# MICRO.net
KiCad netlist of a schematic drawn in Altium Designer
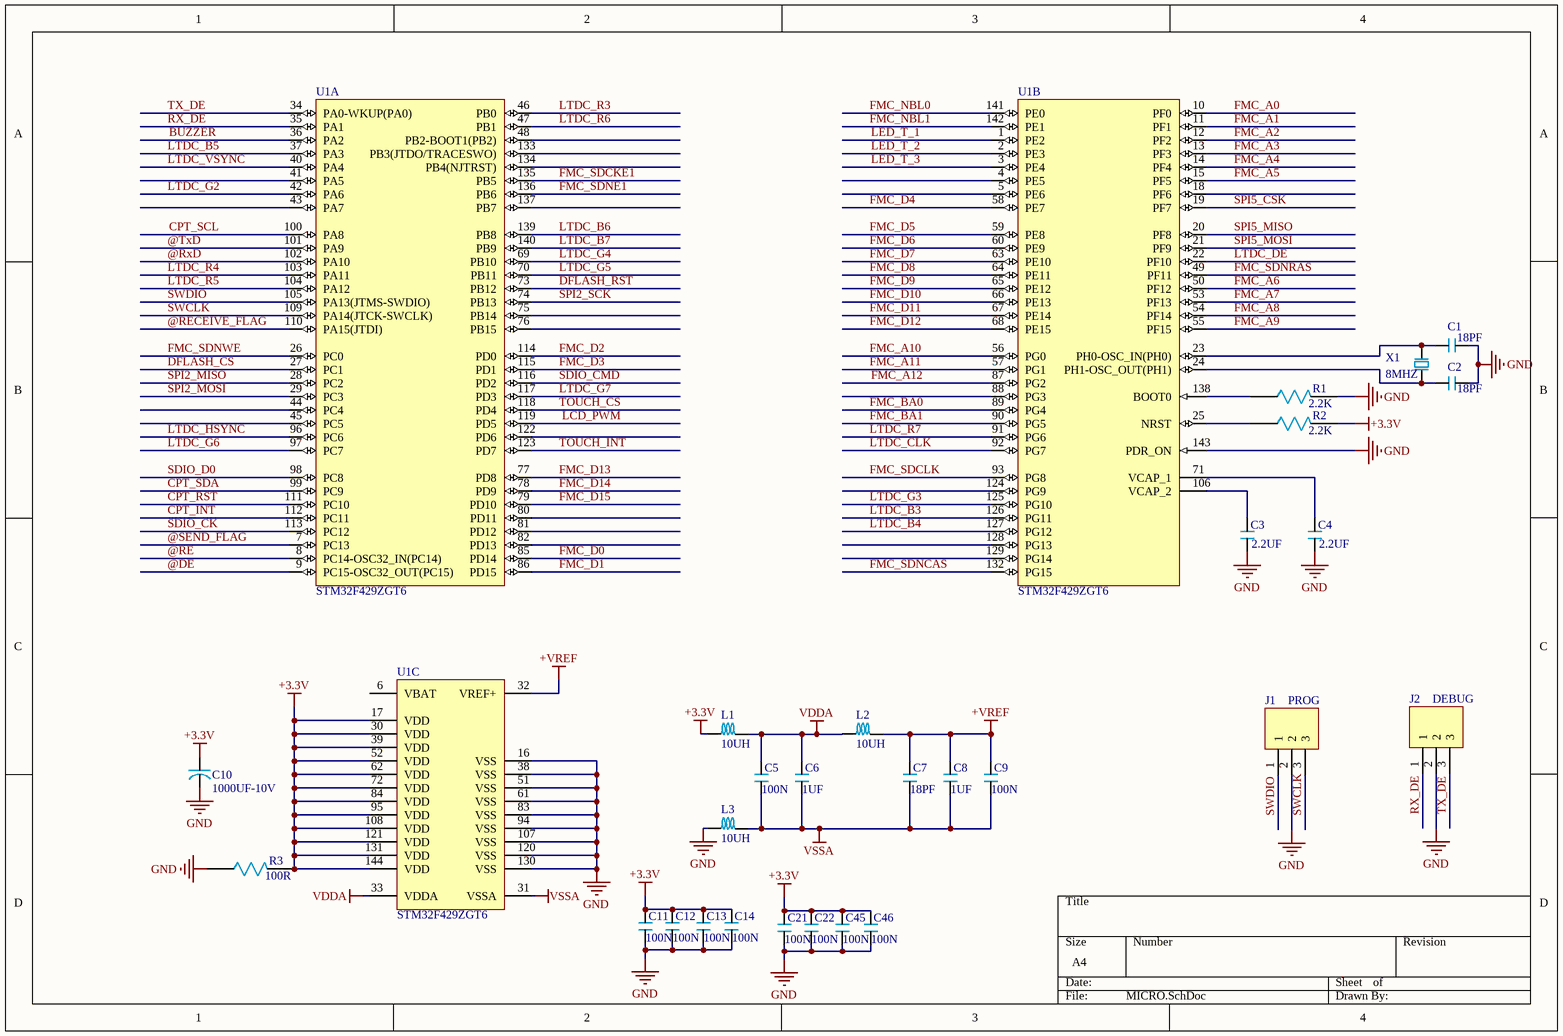
[diagram p0: MICRO.SchDoc]

(export (version "E")
  (design (tool "Eeschema 10.0.6"))
  (components
    (comp (ref "C1") (value "18PF") (footprint "0603") (libsource (lib "R_L_C_V") (part "CAP")))
    (comp (ref "C2") (value "18PF") (footprint "0603") (libsource (lib "R_L_C_V") (part "CAP")))
    (comp (ref "C3") (value "2.2UF") (footprint "1206") (libsource (lib "R_L_C_V") (part "CAP")))
    (comp (ref "C4") (value "2.2UF") (footprint "1206") (libsource (lib "R_L_C_V") (part "CAP")))
    (comp (ref "C5") (value "100N") (footprint "0603") (libsource (lib "R_L_C_V") (part "CAP")))
    (comp (ref "C6") (value "1UF") (footprint "0603") (libsource (lib "R_L_C_V") (part "CAP")))
    (comp (ref "C7") (value "18PF") (footprint "0603") (libsource (lib "R_L_C_V") (part "CAP")))
    (comp (ref "C8") (value "1UF") (footprint "0603") (libsource (lib "R_L_C_V") (part "CAP")))
    (comp (ref "C9") (value "100N") (footprint "0603") (libsource (lib "R_L_C_V") (part "CAP")))
    (comp (ref "C10") (value "1000UF-10V") (footprint "RB.2/.4") (libsource (lib "My_lib") (part "CAP_POL")))
    (comp (ref "C11") (value "100N") (footprint "0603") (libsource (lib "R_L_C_V") (part "CAP")))
    (comp (ref "C12") (value "100N") (footprint "0603") (libsource (lib "R_L_C_V") (part "CAP")))
    (comp (ref "C13") (value "100N") (footprint "0603") (libsource (lib "R_L_C_V") (part "CAP")))
    (comp (ref "C14") (value "100N") (footprint "0603") (libsource (lib "R_L_C_V") (part "CAP")))
    (comp (ref "C21") (value "100N") (footprint "0603") (libsource (lib "R_L_C_V") (part "CAP")))
    (comp (ref "C22") (value "100N") (footprint "0603") (libsource (lib "R_L_C_V") (part "CAP")))
    (comp (ref "C45") (value "100N") (footprint "0603") (libsource (lib "R_L_C_V") (part "CAP")))
    (comp (ref "C46") (value "100N") (footprint "0603") (libsource (lib "R_L_C_V") (part "CAP")))
    (comp (ref "J1") (value "PROG") (footprint "SIP3") (libsource (lib "My_lib") (part "SIP3")))
    (comp (ref "J2") (value "DEBUG") (footprint "SIP3") (libsource (lib "My_lib") (part "SIP3")))
    (comp (ref "L1") (value "10UH") (footprint "1206") (libsource (lib "R_L_C_V") (part "SELF")))
    (comp (ref "L2") (value "10UH") (footprint "1206") (libsource (lib "R_L_C_V") (part "SELF")))
    (comp (ref "L3") (value "10UH") (footprint "1206") (libsource (lib "R_L_C_V") (part "SELF")))
    (comp (ref "R1") (value "2.2K") (footprint "0603") (libsource (lib "My_lib") (part "RES")))
    (comp (ref "R2") (value "2.2K") (footprint "0603") (libsource (lib "My_lib") (part "RES")))
    (comp (ref "R3") (value "100R") (footprint "1206") (libsource (lib "My_lib") (part "RES")))
    (comp (ref "U1")
      (value "STM32F429ZGT6")
      (footprint "STM-LQFP144_N")
      (fields (field (name "MANUFACTURER") "STMicroelectronics"))
      (libsource (lib "STMicroelectronics STM32 F4") (part "STM32F429ZGT6"))
    )
    (comp (ref "X1") (value "8MHZ") (footprint "XTAL_1") (libsource (lib "My_lib") (part "XTAL")))
  )
  (nets
    (net (code "1") (name "+3.3V") (class "Default")
      (node (ref "C10") (pin "1") (pintype "passive"))
      (node (ref "C11") (pin "2") (pintype "passive"))
      (node (ref "C12") (pin "2") (pintype "passive"))
      (node (ref "C13") (pin "2") (pintype "passive"))
      (node (ref "C14") (pin "2") (pintype "passive"))
      (node (ref "C21") (pin "2") (pintype "passive"))
      (node (ref "C22") (pin "2") (pintype "passive"))
      (node (ref "C45") (pin "2") (pintype "passive"))
      (node (ref "C46") (pin "2") (pintype "passive"))
      (node (ref "L1") (pin "1") (pintype "passive"))
      (node (ref "R2") (pin "2") (pintype "passive"))
      (node (ref "R3") (pin "2") (pintype "passive"))
      (node (ref "U1") (pin "108") (pinfunction "VDD_108") (pintype "power_in"))
      (node (ref "U1") (pin "121") (pinfunction "VDD_121") (pintype "power_in"))
      (node (ref "U1") (pin "131") (pinfunction "VDD_131") (pintype "power_in"))
      (node (ref "U1") (pin "144") (pinfunction "VDD_144") (pintype "power_in"))
      (node (ref "U1") (pin "17") (pinfunction "VDD_17") (pintype "power_in"))
      (node (ref "U1") (pin "30") (pinfunction "VDD_30") (pintype "power_in"))
      (node (ref "U1") (pin "39") (pinfunction "VDD_39") (pintype "power_in"))
      (node (ref "U1") (pin "52") (pinfunction "VDD_52") (pintype "power_in"))
      (node (ref "U1") (pin "62") (pinfunction "VDD_62") (pintype "power_in"))
      (node (ref "U1") (pin "72") (pinfunction "VDD_72") (pintype "power_in"))
      (node (ref "U1") (pin "84") (pinfunction "VDD_84") (pintype "power_in"))
      (node (ref "U1") (pin "95") (pinfunction "VDD_95") (pintype "power_in"))
    )
    (net (code "2") (name "+VREF") (class "Default")
      (node (ref "C7") (pin "2") (pintype "passive"))
      (node (ref "C8") (pin "2") (pintype "passive"))
      (node (ref "C9") (pin "2") (pintype "passive"))
      (node (ref "L2") (pin "2") (pintype "passive"))
      (node (ref "U1") (pin "32") (pinfunction "VREF+_32") (pintype "power_in"))
    )
    (net (code "3") (name "/@DE") (class "Default")
      (node (ref "U1") (pin "9") (pinfunction "PC15-OSC32_OUT(PC15)_9") (pintype "bidirectional"))
    )
    (net (code "4") (name "/@RE") (class "Default")
      (node (ref "U1") (pin "8") (pinfunction "PC14-OSC32_IN(PC14)_8") (pintype "bidirectional"))
    )
    (net (code "5") (name "/@RECEIVE_FLAG") (class "Default")
      (node (ref "U1") (pin "110") (pinfunction "PA15(JTDI)_110") (pintype "bidirectional"))
    )
    (net (code "6") (name "/@RxD") (class "Default")
      (node (ref "U1") (pin "102") (pinfunction "PA10_102") (pintype "bidirectional"))
    )
    (net (code "7") (name "/@SEND_FLAG") (class "Default")
      (node (ref "U1") (pin "7") (pinfunction "PC13_7") (pintype "bidirectional"))
    )
    (net (code "8") (name "/@TxD") (class "Default")
      (node (ref "U1") (pin "101") (pinfunction "PA9_101") (pintype "bidirectional"))
    )
    (net (code "9") (name "/BUZZER") (class "Default")
      (node (ref "U1") (pin "36") (pinfunction "PA2_36") (pintype "bidirectional"))
    )
    (net (code "10") (name "/CPT_INT") (class "Default")
      (node (ref "U1") (pin "112") (pinfunction "PC11_112") (pintype "bidirectional"))
    )
    (net (code "11") (name "/CPT_RST") (class "Default")
      (node (ref "U1") (pin "111") (pinfunction "PC10_111") (pintype "bidirectional"))
    )
    (net (code "12") (name "/CPT_SCL") (class "Default")
      (node (ref "U1") (pin "100") (pinfunction "PA8_100") (pintype "bidirectional"))
    )
    (net (code "13") (name "/CPT_SDA") (class "Default")
      (node (ref "U1") (pin "99") (pinfunction "PC9_99") (pintype "bidirectional"))
    )
    (net (code "14") (name "/DFLASH_CS") (class "Default")
      (node (ref "U1") (pin "27") (pinfunction "PC1_27") (pintype "bidirectional"))
    )
    (net (code "15") (name "/DFLASH_RST") (class "Default")
      (node (ref "U1") (pin "73") (pinfunction "PB12_73") (pintype "bidirectional"))
    )
    (net (code "16") (name "/FMC_A0") (class "Default")
      (node (ref "U1") (pin "10") (pinfunction "PF0_10") (pintype "bidirectional"))
    )
    (net (code "17") (name "/FMC_A1") (class "Default")
      (node (ref "U1") (pin "11") (pinfunction "PF1_11") (pintype "bidirectional"))
    )
    (net (code "18") (name "/FMC_A2") (class "Default")
      (node (ref "U1") (pin "12") (pinfunction "PF2_12") (pintype "bidirectional"))
    )
    (net (code "19") (name "/FMC_A3") (class "Default")
      (node (ref "U1") (pin "13") (pinfunction "PF3_13") (pintype "bidirectional"))
    )
    (net (code "20") (name "/FMC_A4") (class "Default")
      (node (ref "U1") (pin "14") (pinfunction "PF4_14") (pintype "bidirectional"))
    )
    (net (code "21") (name "/FMC_A5") (class "Default")
      (node (ref "U1") (pin "15") (pinfunction "PF5_15") (pintype "bidirectional"))
    )
    (net (code "22") (name "/FMC_A6") (class "Default")
      (node (ref "U1") (pin "50") (pinfunction "PF12_50") (pintype "bidirectional"))
    )
    (net (code "23") (name "/FMC_A7") (class "Default")
      (node (ref "U1") (pin "53") (pinfunction "PF13_53") (pintype "bidirectional"))
    )
    (net (code "24") (name "/FMC_A8") (class "Default")
      (node (ref "U1") (pin "54") (pinfunction "PF14_54") (pintype "bidirectional"))
    )
    (net (code "25") (name "/FMC_A9") (class "Default")
      (node (ref "U1") (pin "55") (pinfunction "PF15_55") (pintype "bidirectional"))
    )
    (net (code "26") (name "/FMC_A10") (class "Default")
      (node (ref "U1") (pin "56") (pinfunction "PG0_56") (pintype "bidirectional"))
    )
    (net (code "27") (name "/FMC_A11") (class "Default")
      (node (ref "U1") (pin "57") (pinfunction "PG1_57") (pintype "bidirectional"))
    )
    (net (code "28") (name "/FMC_A12") (class "Default")
      (node (ref "U1") (pin "87") (pinfunction "PG2_87") (pintype "bidirectional"))
    )
    (net (code "29") (name "/FMC_BA0") (class "Default")
      (node (ref "U1") (pin "89") (pinfunction "PG4_89") (pintype "bidirectional"))
    )
    (net (code "30") (name "/FMC_BA1") (class "Default")
      (node (ref "U1") (pin "90") (pinfunction "PG5_90") (pintype "bidirectional"))
    )
    (net (code "31") (name "/FMC_D0") (class "Default")
      (node (ref "U1") (pin "85") (pinfunction "PD14_85") (pintype "bidirectional"))
    )
    (net (code "32") (name "/FMC_D1") (class "Default")
      (node (ref "U1") (pin "86") (pinfunction "PD15_86") (pintype "bidirectional"))
    )
    (net (code "33") (name "/FMC_D2") (class "Default")
      (node (ref "U1") (pin "114") (pinfunction "PD0_114") (pintype "bidirectional"))
    )
    (net (code "34") (name "/FMC_D3") (class "Default")
      (node (ref "U1") (pin "115") (pinfunction "PD1_115") (pintype "bidirectional"))
    )
    (net (code "35") (name "/FMC_D4") (class "Default")
      (node (ref "U1") (pin "58") (pinfunction "PE7_58") (pintype "bidirectional"))
    )
    (net (code "36") (name "/FMC_D5") (class "Default")
      (node (ref "U1") (pin "59") (pinfunction "PE8_59") (pintype "bidirectional"))
    )
    (net (code "37") (name "/FMC_D6") (class "Default")
      (node (ref "U1") (pin "60") (pinfunction "PE9_60") (pintype "bidirectional"))
    )
    (net (code "38") (name "/FMC_D7") (class "Default")
      (node (ref "U1") (pin "63") (pinfunction "PE10_63") (pintype "bidirectional"))
    )
    (net (code "39") (name "/FMC_D8") (class "Default")
      (node (ref "U1") (pin "64") (pinfunction "PE11_64") (pintype "bidirectional"))
    )
    (net (code "40") (name "/FMC_D9") (class "Default")
      (node (ref "U1") (pin "65") (pinfunction "PE12_65") (pintype "bidirectional"))
    )
    (net (code "41") (name "/FMC_D10") (class "Default")
      (node (ref "U1") (pin "66") (pinfunction "PE13_66") (pintype "bidirectional"))
    )
    (net (code "42") (name "/FMC_D11") (class "Default")
      (node (ref "U1") (pin "67") (pinfunction "PE14_67") (pintype "bidirectional"))
    )
    (net (code "43") (name "/FMC_D12") (class "Default")
      (node (ref "U1") (pin "68") (pinfunction "PE15_68") (pintype "bidirectional"))
    )
    (net (code "44") (name "/FMC_D13") (class "Default")
      (node (ref "U1") (pin "77") (pinfunction "PD8_77") (pintype "bidirectional"))
    )
    (net (code "45") (name "/FMC_D14") (class "Default")
      (node (ref "U1") (pin "78") (pinfunction "PD9_78") (pintype "bidirectional"))
    )
    (net (code "46") (name "/FMC_D15") (class "Default")
      (node (ref "U1") (pin "79") (pinfunction "PD10_79") (pintype "bidirectional"))
    )
    (net (code "47") (name "/FMC_NBL0") (class "Default")
      (node (ref "U1") (pin "141") (pinfunction "PE0_141") (pintype "bidirectional"))
    )
    (net (code "48") (name "/FMC_NBL1") (class "Default")
      (node (ref "U1") (pin "142") (pinfunction "PE1_142") (pintype "bidirectional"))
    )
    (net (code "49") (name "/FMC_SDCKE1") (class "Default")
      (node (ref "U1") (pin "135") (pinfunction "PB5_135") (pintype "bidirectional"))
    )
    (net (code "50") (name "/FMC_SDCLK") (class "Default")
      (node (ref "U1") (pin "93") (pinfunction "PG8_93") (pintype "bidirectional"))
    )
    (net (code "51") (name "/FMC_SDNCAS") (class "Default")
      (node (ref "U1") (pin "132") (pinfunction "PG15_132") (pintype "bidirectional"))
    )
    (net (code "52") (name "/FMC_SDNE1") (class "Default")
      (node (ref "U1") (pin "136") (pinfunction "PB6_136") (pintype "bidirectional"))
    )
    (net (code "53") (name "/FMC_SDNRAS") (class "Default")
      (node (ref "U1") (pin "49") (pinfunction "PF11_49") (pintype "bidirectional"))
    )
    (net (code "54") (name "/FMC_SDNWE") (class "Default")
      (node (ref "U1") (pin "26") (pinfunction "PC0_26") (pintype "bidirectional"))
    )
    (net (code "55") (name "/LCD_PWM") (class "Default")
      (node (ref "U1") (pin "119") (pinfunction "PD5_119") (pintype "bidirectional"))
    )
    (net (code "56") (name "/LED_T_1") (class "Default")
      (node (ref "U1") (pin "1") (pinfunction "PE2_1") (pintype "bidirectional"))
    )
    (net (code "57") (name "/LED_T_2") (class "Default")
      (node (ref "U1") (pin "2") (pinfunction "PE3_2") (pintype "bidirectional"))
    )
    (net (code "58") (name "/LED_T_3") (class "Default")
      (node (ref "U1") (pin "3") (pinfunction "PE4_3") (pintype "bidirectional"))
    )
    (net (code "59") (name "/LTDC_B3") (class "Default")
      (node (ref "U1") (pin "126") (pinfunction "PG11_126") (pintype "bidirectional"))
    )
    (net (code "60") (name "/LTDC_B4") (class "Default")
      (node (ref "U1") (pin "127") (pinfunction "PG12_127") (pintype "bidirectional"))
    )
    (net (code "61") (name "/LTDC_B5") (class "Default")
      (node (ref "U1") (pin "37") (pinfunction "PA3_37") (pintype "bidirectional"))
    )
    (net (code "62") (name "/LTDC_B6") (class "Default")
      (node (ref "U1") (pin "139") (pinfunction "PB8_139") (pintype "bidirectional"))
    )
    (net (code "63") (name "/LTDC_B7") (class "Default")
      (node (ref "U1") (pin "140") (pinfunction "PB9_140") (pintype "bidirectional"))
    )
    (net (code "64") (name "/LTDC_CLK") (class "Default")
      (node (ref "U1") (pin "92") (pinfunction "PG7_92") (pintype "bidirectional"))
    )
    (net (code "65") (name "/LTDC_DE") (class "Default")
      (node (ref "U1") (pin "22") (pinfunction "PF10_22") (pintype "bidirectional"))
    )
    (net (code "66") (name "/LTDC_G2") (class "Default")
      (node (ref "U1") (pin "42") (pinfunction "PA6_42") (pintype "bidirectional"))
    )
    (net (code "67") (name "/LTDC_G3") (class "Default")
      (node (ref "U1") (pin "125") (pinfunction "PG10_125") (pintype "bidirectional"))
    )
    (net (code "68") (name "/LTDC_G4") (class "Default")
      (node (ref "U1") (pin "69") (pinfunction "PB10_69") (pintype "bidirectional"))
    )
    (net (code "69") (name "/LTDC_G5") (class "Default")
      (node (ref "U1") (pin "70") (pinfunction "PB11_70") (pintype "bidirectional"))
    )
    (net (code "70") (name "/LTDC_G6") (class "Default")
      (node (ref "U1") (pin "97") (pinfunction "PC7_97") (pintype "bidirectional"))
    )
    (net (code "71") (name "/LTDC_G7") (class "Default")
      (node (ref "U1") (pin "117") (pinfunction "PD3_117") (pintype "bidirectional"))
    )
    (net (code "72") (name "/LTDC_HSYNC") (class "Default")
      (node (ref "U1") (pin "96") (pinfunction "PC6_96") (pintype "bidirectional"))
    )
    (net (code "73") (name "/LTDC_R3") (class "Default")
      (node (ref "U1") (pin "46") (pinfunction "PB0_46") (pintype "bidirectional"))
    )
    (net (code "74") (name "/LTDC_R4") (class "Default")
      (node (ref "U1") (pin "103") (pinfunction "PA11_103") (pintype "bidirectional"))
    )
    (net (code "75") (name "/LTDC_R5") (class "Default")
      (node (ref "U1") (pin "104") (pinfunction "PA12_104") (pintype "bidirectional"))
    )
    (net (code "76") (name "/LTDC_R6") (class "Default")
      (node (ref "U1") (pin "47") (pinfunction "PB1_47") (pintype "bidirectional"))
    )
    (net (code "77") (name "/LTDC_R7") (class "Default")
      (node (ref "U1") (pin "91") (pinfunction "PG6_91") (pintype "bidirectional"))
    )
    (net (code "78") (name "/LTDC_VSYNC") (class "Default")
      (node (ref "U1") (pin "40") (pinfunction "PA4_40") (pintype "bidirectional"))
    )
    (net (code "79") (name "/RX_DE") (class "Default")
      (node (ref "J2") (pin "1") (pinfunction "1_1") (pintype "passive"))
      (node (ref "U1") (pin "35") (pinfunction "PA1_35") (pintype "bidirectional"))
    )
    (net (code "80") (name "/SDIO_CK") (class "Default")
      (node (ref "U1") (pin "113") (pinfunction "PC12_113") (pintype "bidirectional"))
    )
    (net (code "81") (name "/SDIO_CMD") (class "Default")
      (node (ref "U1") (pin "116") (pinfunction "PD2_116") (pintype "bidirectional"))
    )
    (net (code "82") (name "/SDIO_D0") (class "Default")
      (node (ref "U1") (pin "98") (pinfunction "PC8_98") (pintype "bidirectional"))
    )
    (net (code "83") (name "/SPI2_MISO") (class "Default")
      (node (ref "U1") (pin "28") (pinfunction "PC2_28") (pintype "bidirectional"))
    )
    (net (code "84") (name "/SPI2_MOSI") (class "Default")
      (node (ref "U1") (pin "29") (pinfunction "PC3_29") (pintype "bidirectional"))
    )
    (net (code "85") (name "/SPI2_SCK") (class "Default")
      (node (ref "U1") (pin "74") (pinfunction "PB13_74") (pintype "bidirectional"))
    )
    (net (code "86") (name "/SPI5_CSK") (class "Default")
      (node (ref "U1") (pin "19") (pinfunction "PF7_19") (pintype "bidirectional"))
    )
    (net (code "87") (name "/SPI5_MISO") (class "Default")
      (node (ref "U1") (pin "20") (pinfunction "PF8_20") (pintype "bidirectional"))
    )
    (net (code "88") (name "/SPI5_MOSI") (class "Default")
      (node (ref "U1") (pin "21") (pinfunction "PF9_21") (pintype "bidirectional"))
    )
    (net (code "89") (name "/SWCLK") (class "Default")
      (node (ref "J1") (pin "3") (pinfunction "3_3") (pintype "passive"))
      (node (ref "U1") (pin "109") (pinfunction "PA14(JTCK-SWCLK)_109") (pintype "bidirectional"))
    )
    (net (code "90") (name "/SWDIO") (class "Default")
      (node (ref "J1") (pin "1") (pinfunction "1_1") (pintype "passive"))
      (node (ref "U1") (pin "105") (pinfunction "PA13(JTMS-SWDIO)_105") (pintype "bidirectional"))
    )
    (net (code "91") (name "/TOUCH_CS") (class "Default")
      (node (ref "U1") (pin "118") (pinfunction "PD4_118") (pintype "bidirectional"))
    )
    (net (code "92") (name "/TOUCH_INT") (class "Default")
      (node (ref "U1") (pin "123") (pinfunction "PD7_123") (pintype "bidirectional"))
    )
    (net (code "93") (name "/TX_DE") (class "Default")
      (node (ref "J2") (pin "3") (pinfunction "3_3") (pintype "passive"))
      (node (ref "U1") (pin "34") (pinfunction "PA0-WKUP(PA0)_34") (pintype "bidirectional"))
    )
    (net (code "94") (name "GND") (class "Default")
      (node (ref "C1") (pin "2") (pintype "passive"))
      (node (ref "C10") (pin "2") (pintype "passive"))
      (node (ref "C11") (pin "1") (pintype "passive"))
      (node (ref "C12") (pin "1") (pintype "passive"))
      (node (ref "C13") (pin "1") (pintype "passive"))
      (node (ref "C14") (pin "1") (pintype "passive"))
      (node (ref "C2") (pin "2") (pintype "passive"))
      (node (ref "C21") (pin "1") (pintype "passive"))
      (node (ref "C22") (pin "1") (pintype "passive"))
      (node (ref "C3") (pin "1") (pintype "passive"))
      (node (ref "C4") (pin "1") (pintype "passive"))
      (node (ref "C45") (pin "1") (pintype "passive"))
      (node (ref "C46") (pin "1") (pintype "passive"))
      (node (ref "J1") (pin "2") (pinfunction "2_2") (pintype "passive"))
      (node (ref "J2") (pin "2") (pinfunction "2_2") (pintype "passive"))
      (node (ref "L3") (pin "1") (pintype "passive"))
      (node (ref "R1") (pin "2") (pintype "passive"))
      (node (ref "R3") (pin "1") (pintype "passive"))
      (node (ref "U1") (pin "107") (pinfunction "VSS_107") (pintype "power_in"))
      (node (ref "U1") (pin "120") (pinfunction "VSS_120") (pintype "power_in"))
      (node (ref "U1") (pin "130") (pinfunction "VSS_130") (pintype "power_in"))
      (node (ref "U1") (pin "143") (pinfunction "PDR_ON_143") (pintype "input"))
      (node (ref "U1") (pin "16") (pinfunction "VSS_16") (pintype "power_in"))
      (node (ref "U1") (pin "38") (pinfunction "VSS_38") (pintype "power_in"))
      (node (ref "U1") (pin "51") (pinfunction "VSS_51") (pintype "power_in"))
      (node (ref "U1") (pin "61") (pinfunction "VSS_61") (pintype "power_in"))
      (node (ref "U1") (pin "83") (pinfunction "VSS_83") (pintype "power_in"))
      (node (ref "U1") (pin "94") (pinfunction "VSS_94") (pintype "power_in"))
    )
    (net (code "95") (name "Net-(U1B-BOOT0)") (class "Default")
      (node (ref "R1") (pin "1") (pintype "passive"))
      (node (ref "U1") (pin "138") (pinfunction "BOOT0_138") (pintype "input"))
    )
    (net (code "96") (name "Net-(U1B-NRST)") (class "Default")
      (node (ref "R2") (pin "1") (pintype "passive"))
      (node (ref "U1") (pin "25") (pinfunction "NRST_25") (pintype "bidirectional"))
    )
    (net (code "97") (name "Net-(U1B-PH0-OSC_IN(PH0))") (class "Default")
      (node (ref "C1") (pin "1") (pintype "passive"))
      (node (ref "U1") (pin "23") (pinfunction "PH0-OSC_IN(PH0)_23") (pintype "bidirectional"))
      (node (ref "X1") (pin "2") (pintype "passive"))
    )
    (net (code "98") (name "Net-(U1B-PH1-OSC_OUT(PH1))") (class "Default")
      (node (ref "C2") (pin "1") (pintype "passive"))
      (node (ref "U1") (pin "24") (pinfunction "PH1-OSC_OUT(PH1)_24") (pintype "bidirectional"))
      (node (ref "X1") (pin "1") (pintype "passive"))
    )
    (net (code "99") (name "Net-(U1B-VCAP_1)") (class "Default")
      (node (ref "C4") (pin "2") (pintype "passive"))
      (node (ref "U1") (pin "71") (pinfunction "VCAP_1_71") (pintype "power_in"))
    )
    (net (code "100") (name "Net-(U1B-VCAP_2)") (class "Default")
      (node (ref "C3") (pin "2") (pintype "passive"))
      (node (ref "U1") (pin "106") (pinfunction "VCAP_2_106") (pintype "power_in"))
    )
    (net (code "101") (name "VDDA") (class "Default")
      (node (ref "C5") (pin "2") (pintype "passive"))
      (node (ref "C6") (pin "2") (pintype "passive"))
      (node (ref "L1") (pin "2") (pintype "passive"))
      (node (ref "L2") (pin "1") (pintype "passive"))
      (node (ref "U1") (pin "33") (pinfunction "VDDA_33") (pintype "power_in"))
    )
    (net (code "102") (name "VSSA") (class "Default")
      (node (ref "C5") (pin "1") (pintype "passive"))
      (node (ref "C6") (pin "1") (pintype "passive"))
      (node (ref "C7") (pin "1") (pintype "passive"))
      (node (ref "C8") (pin "1") (pintype "passive"))
      (node (ref "C9") (pin "1") (pintype "passive"))
      (node (ref "L3") (pin "2") (pintype "passive"))
      (node (ref "U1") (pin "31") (pinfunction "VSSA_31") (pintype "power_in"))
    )
    (net (code "103") (name "unconnected-(U1A-PA5-Pad41)") (class "Default")
      (node (ref "U1") (pin "41") (pinfunction "PA5_41") (pintype "bidirectional"))
    )
    (net (code "104") (name "unconnected-(U1A-PA7-Pad43)") (class "Default")
      (node (ref "U1") (pin "43") (pinfunction "PA7_43") (pintype "bidirectional"))
    )
    (net (code "105") (name "unconnected-(U1A-PB2-BOOT1(PB2)-Pad48)") (class "Default")
      (node (ref "U1") (pin "48") (pinfunction "PB2-BOOT1(PB2)_48") (pintype "bidirectional"))
    )
    (net (code "106") (name "unconnected-(U1A-PB3(JTDO{slash}TRACESWO)-Pad133)") (class "Default")
      (node (ref "U1") (pin "133") (pinfunction "PB3(JTDO/TRACESWO)_133") (pintype "bidirectional"))
    )
    (net (code "107") (name "unconnected-(U1A-PB4(NJTRST)-Pad134)") (class "Default")
      (node (ref "U1") (pin "134") (pinfunction "PB4(NJTRST)_134") (pintype "bidirectional"))
    )
    (net (code "108") (name "unconnected-(U1A-PB7-Pad137)") (class "Default")
      (node (ref "U1") (pin "137") (pinfunction "PB7_137") (pintype "bidirectional"))
    )
    (net (code "109") (name "unconnected-(U1A-PB14-Pad75)") (class "Default")
      (node (ref "U1") (pin "75") (pinfunction "PB14_75") (pintype "bidirectional"))
    )
    (net (code "110") (name "unconnected-(U1A-PB15-Pad76)") (class "Default")
      (node (ref "U1") (pin "76") (pinfunction "PB15_76") (pintype "bidirectional"))
    )
    (net (code "111") (name "unconnected-(U1A-PC4-Pad44)") (class "Default")
      (node (ref "U1") (pin "44") (pinfunction "PC4_44") (pintype "bidirectional"))
    )
    (net (code "112") (name "unconnected-(U1A-PC5-Pad45)") (class "Default")
      (node (ref "U1") (pin "45") (pinfunction "PC5_45") (pintype "bidirectional"))
    )
    (net (code "113") (name "unconnected-(U1A-PD6-Pad122)") (class "Default")
      (node (ref "U1") (pin "122") (pinfunction "PD6_122") (pintype "bidirectional"))
    )
    (net (code "114") (name "unconnected-(U1A-PD11-Pad80)") (class "Default")
      (node (ref "U1") (pin "80") (pinfunction "PD11_80") (pintype "bidirectional"))
    )
    (net (code "115") (name "unconnected-(U1A-PD12-Pad81)") (class "Default")
      (node (ref "U1") (pin "81") (pinfunction "PD12_81") (pintype "bidirectional"))
    )
    (net (code "116") (name "unconnected-(U1A-PD13-Pad82)") (class "Default")
      (node (ref "U1") (pin "82") (pinfunction "PD13_82") (pintype "bidirectional"))
    )
    (net (code "117") (name "unconnected-(U1B-PE5-Pad4)") (class "Default")
      (node (ref "U1") (pin "4") (pinfunction "PE5_4") (pintype "bidirectional"))
    )
    (net (code "118") (name "unconnected-(U1B-PE6-Pad5)") (class "Default")
      (node (ref "U1") (pin "5") (pinfunction "PE6_5") (pintype "bidirectional"))
    )
    (net (code "119") (name "unconnected-(U1B-PF6-Pad18)") (class "Default")
      (node (ref "U1") (pin "18") (pinfunction "PF6_18") (pintype "bidirectional"))
    )
    (net (code "120") (name "unconnected-(U1B-PG3-Pad88)") (class "Default")
      (node (ref "U1") (pin "88") (pinfunction "PG3_88") (pintype "bidirectional"))
    )
    (net (code "121") (name "unconnected-(U1B-PG9-Pad124)") (class "Default")
      (node (ref "U1") (pin "124") (pinfunction "PG9_124") (pintype "bidirectional"))
    )
    (net (code "122") (name "unconnected-(U1B-PG13-Pad128)") (class "Default")
      (node (ref "U1") (pin "128") (pinfunction "PG13_128") (pintype "bidirectional"))
    )
    (net (code "123") (name "unconnected-(U1B-PG14-Pad129)") (class "Default")
      (node (ref "U1") (pin "129") (pinfunction "PG14_129") (pintype "bidirectional"))
    )
    (net (code "124") (name "unconnected-(U1C-VBAT-Pad6)") (class "Default")
      (node (ref "U1") (pin "6") (pinfunction "VBAT_6") (pintype "power_in"))
    )
  )
)
